# design.net
KiCad netlist of a schematic drawn in Altium Designer
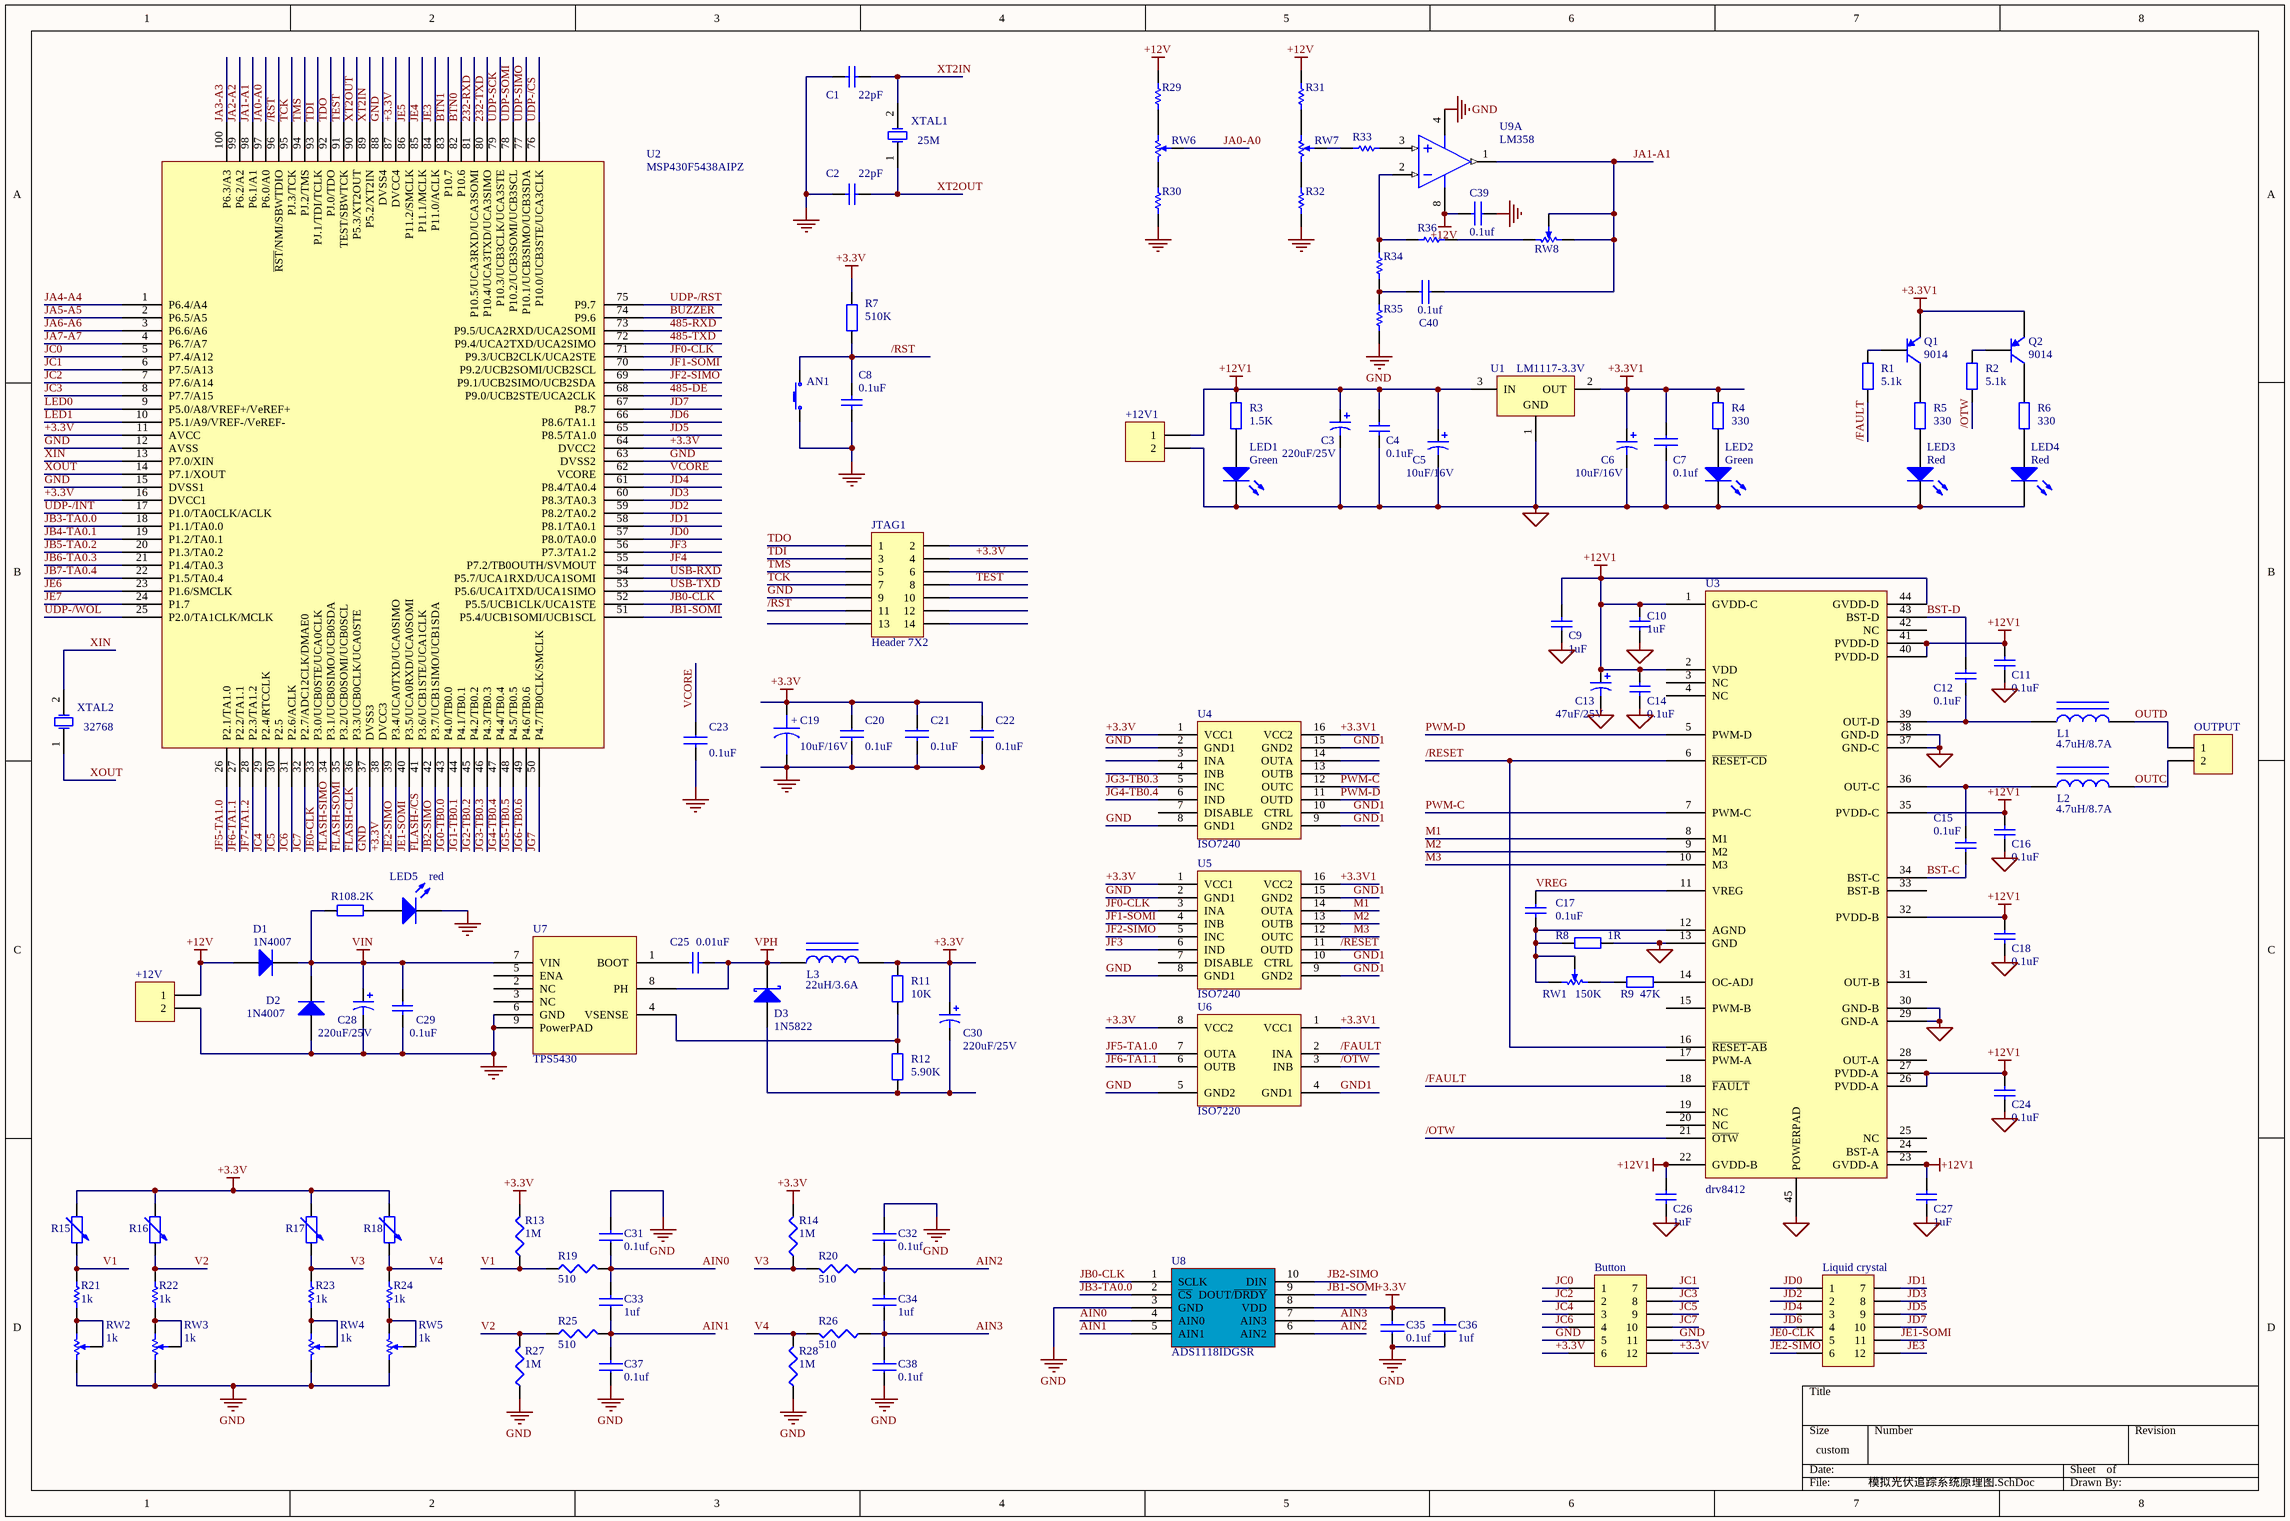
[diagram p0: 模拟光伏追踪系统原理图.SchDoc]

(export (version "E")
  (design (tool "Eeschema 10.0.6"))
  (components
    (comp (ref "+12V")
      (value "Comment")
      (footprint "接线端子")
      (description "Header, 2-Pin")
      (fields (field (name "PUBLISHER") "Altium Limited"))
      (libsource (lib "Miscellaneous Connectors") (part "Header 2"))
    )
    (comp (ref "+12V1")
      (value "Comment")
      (footprint "接线端子")
      (description "Header, 2-Pin")
      (fields (field (name "PUBLISHER") "Altium Limited"))
      (libsource (lib "Miscellaneous Connectors") (part "Header 2"))
    )
    (comp (ref "AN1") (value "key") (footprint "AN6X6") (libsource (lib "*") (part "Key_2")))
    (comp (ref "Button")
      (value "Header 6X2A")
      (footprint "PMOD")
      (description "Header, 6-Pin, Dual row")
      (fields (field (name "PUBLISHER") "Altium Limited"))
      (libsource (lib "Miscellaneous Connectors") (part "Header 6X2A"))
    )
    (comp (ref "C1")
      (value "22pF")
      (footprint "0805C")
      (description "Capacitor")
      (fields (field (name "Comment") "Cap") (field (name "PUBLISHER") "Altium Limited"))
      (libsource (lib "Miscellaneous Devices") (part "Cap"))
    )
    (comp (ref "C2")
      (value "22pF")
      (footprint "0805C")
      (description "Capacitor")
      (fields (field (name "Comment") "Cap") (field (name "PUBLISHER") "Altium Limited"))
      (libsource (lib "Miscellaneous Devices") (part "Cap"))
    )
    (comp (ref "C3")
      (value "220uF/25V")
      (footprint "CD-220uF-25V")
      (description "Polarized Capacitor (Radial)")
      (fields (field (name "Comment") "Cap Pol1") (field (name "PUBLISHER") "Altium Limited"))
      (libsource (lib "Miscellaneous Devices") (part "Cap Pol1"))
    )
    (comp (ref "C4")
      (value "0.1uF")
      (footprint "0805C")
      (description "Capacitor")
      (fields (field (name "Comment") "Cap") (field (name "PUBLISHER") "Altium Limited"))
      (libsource (lib "Miscellaneous Devices") (part "Cap"))
    )
    (comp (ref "C5")
      (value "10uF/16V")
      (footprint "A3216")
      (description "Polarized Capacitor (Radial)")
      (fields (field (name "PUBLISHER") "Altium Limited"))
      (libsource (lib "Miscellaneous Devices") (part "Cap Pol1"))
    )
    (comp (ref "C6")
      (value "10uF/16V")
      (footprint "A3216")
      (description "Polarized Capacitor (Radial)")
      (fields (field (name "PUBLISHER") "Altium Limited"))
      (libsource (lib "Miscellaneous Devices") (part "Cap Pol1"))
    )
    (comp (ref "C7") (value "0.1uf") (footprint "0805C") (libsource (lib "General") (part "Cap")))
    (comp (ref "C8")
      (value "0.1uF")
      (footprint "0805C")
      (description "Capacitor")
      (fields (field (name "Comment") "Cap") (field (name "PUBLISHER") "Altium Limited"))
      (libsource (lib "Miscellaneous Devices") (part "Cap"))
    )
    (comp (ref "C9")
      (value "1uF")
      (footprint "0805C")
      (description "Capacitor")
      (fields (field (name "Comment") "Cap") (field (name "PUBLISHER") "Altium Limited"))
      (libsource (lib "Miscellaneous Devices") (part "Cap"))
    )
    (comp (ref "C10")
      (value "1uF")
      (footprint "0805C")
      (description "Capacitor")
      (fields (field (name "Comment") "Cap") (field (name "PUBLISHER") "Altium Limited"))
      (libsource (lib "Miscellaneous Devices") (part "Cap"))
    )
    (comp (ref "C11")
      (value "0.1uF")
      (footprint "0805C")
      (description "Capacitor")
      (fields (field (name "Comment") "Cap") (field (name "PUBLISHER") "Altium Limited"))
      (libsource (lib "Miscellaneous Devices") (part "Cap"))
    )
    (comp (ref "C12")
      (value "0.1uF")
      (footprint "0805C")
      (description "Capacitor")
      (fields (field (name "Comment") "Cap") (field (name "PUBLISHER") "Altium Limited"))
      (libsource (lib "Miscellaneous Devices") (part "Cap"))
    )
    (comp (ref "C13")
      (value "47uF/25V")
      (footprint "CD-220uF-25V")
      (description "Polarized Capacitor (Radial)")
      (fields (field (name "Comment") "Cap Pol1") (field (name "PUBLISHER") "Altium Limited"))
      (libsource (lib "Miscellaneous Devices") (part "Cap Pol1"))
    )
    (comp (ref "C14")
      (value "0.1uF")
      (footprint "0805C")
      (description "Capacitor")
      (fields (field (name "Comment") "Cap") (field (name "PUBLISHER") "Altium Limited"))
      (libsource (lib "Miscellaneous Devices") (part "Cap"))
    )
    (comp (ref "C15")
      (value "0.1uF")
      (footprint "0805C")
      (description "Capacitor")
      (fields (field (name "Comment") "Cap") (field (name "PUBLISHER") "Altium Limited"))
      (libsource (lib "Miscellaneous Devices") (part "Cap"))
    )
    (comp (ref "C16")
      (value "0.1uF")
      (footprint "0805C")
      (description "Capacitor")
      (fields (field (name "Comment") "Cap") (field (name "PUBLISHER") "Altium Limited"))
      (libsource (lib "Miscellaneous Devices") (part "Cap"))
    )
    (comp (ref "C17")
      (value "0.1uF")
      (footprint "0805C")
      (description "Capacitor")
      (fields (field (name "Comment") "Cap") (field (name "PUBLISHER") "Altium Limited"))
      (libsource (lib "Miscellaneous Devices") (part "Cap"))
    )
    (comp (ref "C18")
      (value "0.1uF")
      (footprint "0805C")
      (description "Capacitor")
      (fields (field (name "Comment") "Cap") (field (name "PUBLISHER") "Altium Limited"))
      (libsource (lib "Miscellaneous Devices") (part "Cap"))
    )
    (comp (ref "C19")
      (value "10uF/16V")
      (footprint "A3216")
      (description "Capacitor")
      (libsource (lib "*") (part "CAPACITOR POL"))
    )
    (comp (ref "C20") (value "0.1uF") (footprint "0805C") (libsource (lib "*") (part "CC_0.1U_16V_X7R_0603")))
    (comp (ref "C21") (value "0.1uF") (footprint "0805C") (libsource (lib "*") (part "CC_0.1U_16V_X7R_0603")))
    (comp (ref "C22") (value "0.1uF") (footprint "0805C") (libsource (lib "*") (part "CC_0.1U_16V_X7R_0603")))
    (comp (ref "C23")
      (value "0.1uF")
      (footprint "0805C")
      (libsource (lib "*") (part "CC_0.01U_16V_X7R_0603"))
    )
    (comp (ref "C24")
      (value "0.1uF")
      (footprint "0805C")
      (description "Capacitor")
      (fields (field (name "Comment") "Cap") (field (name "PUBLISHER") "Altium Limited"))
      (libsource (lib "Miscellaneous Devices") (part "Cap"))
    )
    (comp (ref "C25")
      (value "0.01uF")
      (footprint "0805C")
      (description "Capacitor")
      (fields (field (name "Comment") "Cap") (field (name "PUBLISHER") "Altium Limited"))
      (libsource (lib "Miscellaneous Devices") (part "Cap"))
    )
    (comp (ref "C26")
      (value "1uF")
      (footprint "0805C")
      (description "Capacitor")
      (fields (field (name "Comment") "Cap") (field (name "PUBLISHER") "Altium Limited"))
      (libsource (lib "Miscellaneous Devices") (part "Cap"))
    )
    (comp (ref "C27")
      (value "1uF")
      (footprint "0805C")
      (description "Capacitor")
      (fields (field (name "Comment") "Cap") (field (name "PUBLISHER") "Altium Limited"))
      (libsource (lib "Miscellaneous Devices") (part "Cap"))
    )
    (comp (ref "C28")
      (value "220uF/25V")
      (footprint "CD-220uF-25V")
      (description "Polarized Capacitor (Radial)")
      (fields (field (name "Comment") "Cap Pol1") (field (name "PUBLISHER") "Altium Limited"))
      (libsource (lib "Miscellaneous Devices") (part "Cap Pol1"))
    )
    (comp (ref "C29")
      (value "0.1uF")
      (footprint "0805C")
      (description "Capacitor")
      (fields (field (name "Comment") "Cap") (field (name "PUBLISHER") "Altium Limited"))
      (libsource (lib "Miscellaneous Devices") (part "Cap"))
    )
    (comp (ref "C30")
      (value "220uF/25V")
      (footprint "CD-220uF-25V")
      (description "Polarized Capacitor (Radial)")
      (fields (field (name "Comment") "Cap Pol1") (field (name "PUBLISHER") "Altium Limited"))
      (libsource (lib "Miscellaneous Devices") (part "Cap Pol1"))
    )
    (comp (ref "C31") (value "0.1uf") (footprint "0805C") (libsource (lib "General") (part "Cap")))
    (comp (ref "C32") (value "0.1uf") (footprint "0805C") (libsource (lib "General") (part "Cap")))
    (comp (ref "C33") (value "1uf") (footprint "0805C") (libsource (lib "General") (part "Cap")))
    (comp (ref "C34") (value "1uf") (footprint "0805C") (libsource (lib "General") (part "Cap")))
    (comp (ref "C35") (value "0.1uf") (footprint "0805C") (libsource (lib "General") (part "Cap")))
    (comp (ref "C36") (value "1uf") (footprint "0805C") (libsource (lib "General") (part "Cap")))
    (comp (ref "C37") (value "0.1uf") (footprint "0805C") (libsource (lib "General") (part "Cap")))
    (comp (ref "C38") (value "0.1uf") (footprint "0805C") (libsource (lib "General") (part "Cap")))
    (comp (ref "C39") (value "0.1uf") (footprint "0805C") (libsource (lib "General") (part "Cap")))
    (comp (ref "C40") (value "0.1uf") (footprint "0805C") (libsource (lib "General") (part "Cap")))
    (comp (ref "D1") (value "1N4007") (footprint "D1206") (libsource (lib "Sch") (part "DIODE")))
    (comp (ref "D2") (value "1N4007") (footprint "D1206") (libsource (lib "Sch") (part "DIODE")))
    (comp (ref "D3")
      (value "D Schottky")
      (footprint "D1206")
      (description "Schottky Diode")
      (fields (field (name "ALTIUM_UNNAMED_1") "1N5822") (field (name "PUBLISHER") "Altium Limited"))
      (libsource (lib "Miscellaneous Devices") (part "D Schottky"))
    )
    (comp (ref "JTAG1")
      (value "Header 7X2")
      (footprint "HDR2X7")
      (description "Header, 7-Pin, Dual row")
      (fields (field (name "PUBLISHER") "Altium Limited"))
      (libsource (lib "Miscellaneous Connectors") (part "Header 7X2"))
    )
    (comp (ref "L1")
      (value "4.7uH/8.7A")
      (footprint "CDRH127")
      (description "Magnetic-Core Inductor")
      (fields (field (name "Comment") "Inductor Iron") (field (name "PUBLISHER") "Altium Limited"))
      (libsource (lib "Miscellaneous Devices") (part "Inductor Iron"))
    )
    (comp (ref "L2")
      (value "4.7uH/8.7A")
      (footprint "CDRH127")
      (description "Magnetic-Core Inductor")
      (fields (field (name "Comment") "Inductor Iron") (field (name "PUBLISHER") "Altium Limited"))
      (libsource (lib "Miscellaneous Devices") (part "Inductor Iron"))
    )
    (comp (ref "L3")
      (value "22uH/3.6A")
      (footprint "CDRH127")
      (description "Magnetic-Core Inductor")
      (fields (field (name "Comment") "Inductor Iron") (field (name "PUBLISHER") "Altium Limited"))
      (libsource (lib "Miscellaneous Devices") (part "Inductor Iron"))
    )
    (comp (ref "LED1")
      (value "~")
      (footprint "0805LED")
      (description "Typical RED, GREEN, YELLOW, AMBER GaAs LED")
      (fields (field (name "ALTIUM_UNNAMED_1") "Green") (field (name "PUBLISHER") "Altium Limited"))
      (libsource (lib "Miscellaneous Devices") (part "LED2"))
    )
    (comp (ref "LED2")
      (value "~")
      (footprint "0805LED")
      (description "Typical RED, GREEN, YELLOW, AMBER GaAs LED")
      (fields (field (name "ALTIUM_UNNAMED_1") "Green") (field (name "PUBLISHER") "Altium Limited"))
      (libsource (lib "Miscellaneous Devices") (part "LED2"))
    )
    (comp (ref "LED3")
      (value "~")
      (footprint "0805LED")
      (description "Typical RED, GREEN, YELLOW, AMBER GaAs LED")
      (fields (field (name "ALTIUM_UNNAMED_1") "Red") (field (name "PUBLISHER") "Altium Limited"))
      (libsource (lib "Miscellaneous Devices") (part "LED2"))
    )
    (comp (ref "LED4")
      (value "~")
      (footprint "0805LED")
      (description "Typical RED, GREEN, YELLOW, AMBER GaAs LED")
      (fields (field (name "ALTIUM_UNNAMED_1") "Red") (field (name "PUBLISHER") "Altium Limited"))
      (libsource (lib "Miscellaneous Devices") (part "LED2"))
    )
    (comp (ref "LED5")
      (value "~")
      (footprint "0805LED")
      (description "Typical RED, GREEN, YELLOW, AMBER GaAs LED")
      (fields (field (name "ALTIUM_UNNAMED_1") "red") (field (name "PUBLISHER") "Altium Limited"))
      (libsource (lib "Miscellaneous Devices") (part "LED2"))
    )
    (comp (ref "Liquid crystal")
      (value "Header 6X2A")
      (footprint "PMOD")
      (description "Header, 6-Pin, Dual row")
      (fields (field (name "PUBLISHER") "Altium Limited"))
      (libsource (lib "Miscellaneous Connectors") (part "Header 6X2A"))
    )
    (comp (ref "OUTPUT")
      (value "Comment")
      (footprint "接线端子")
      (description "Header, 2-Pin")
      (fields (field (name "PUBLISHER") "Altium Limited"))
      (libsource (lib "") (part "Header 2_1"))
    )
    (comp (ref "Q1")
      (value "9014")
      (footprint "SOT-23B")
      (description "PNP Bipolar Transistor")
      (fields (field (name "PUBLISHER") "Altium Limited"))
      (libsource (lib "Miscellaneous Devices") (part "PNP"))
    )
    (comp (ref "Q2")
      (value "9014")
      (footprint "SOT-23B")
      (description "PNP Bipolar Transistor")
      (fields (field (name "PUBLISHER") "Altium Limited"))
      (libsource (lib "Miscellaneous Devices") (part "PNP"))
    )
    (comp (ref "R1")
      (value "5.1k")
      (footprint "0805R")
      (description "Resistor")
      (fields (field (name "Comment") "Res2") (field (name "PUBLISHER") "Altium Limited"))
      (libsource (lib "") (part "Res2_2"))
    )
    (comp (ref "R2")
      (value "5.1k")
      (footprint "0805R")
      (description "Resistor")
      (fields (field (name "Comment") "Res2") (field (name "PUBLISHER") "Altium Limited"))
      (libsource (lib "") (part "Res2_2"))
    )
    (comp (ref "R3")
      (value "1.5K")
      (footprint "0805R")
      (description "Resistor")
      (fields (field (name "Comment") "Res2") (field (name "PUBLISHER") "Altium Limited"))
      (libsource (lib "Miscellaneous Devices") (part "Res2"))
    )
    (comp (ref "R4")
      (value "330")
      (footprint "0805R")
      (description "Resistor")
      (fields (field (name "Comment") "Res2") (field (name "PUBLISHER") "Altium Limited"))
      (libsource (lib "") (part "Res2_2"))
    )
    (comp (ref "R5")
      (value "330")
      (footprint "0805R")
      (description "Resistor")
      (fields (field (name "Comment") "Res2") (field (name "PUBLISHER") "Altium Limited"))
      (libsource (lib "") (part "Res2_2"))
    )
    (comp (ref "R6")
      (value "330")
      (footprint "0805R")
      (description "Resistor")
      (fields (field (name "Comment") "Res2") (field (name "PUBLISHER") "Altium Limited"))
      (libsource (lib "") (part "Res2_2"))
    )
    (comp (ref "R7")
      (value "510K")
      (footprint "0805R")
      (description "Resistor")
      (fields (field (name "Comment") "Res2") (field (name "PUBLISHER") "Altium Limited"))
      (libsource (lib "Miscellaneous Devices") (part "Res2"))
    )
    (comp (ref "R8")
      (value "1R")
      (footprint "0805R")
      (description "Resistor")
      (fields (field (name "Comment") "Res2") (field (name "PUBLISHER") "Altium Limited"))
      (libsource (lib "") (part "Res2_1"))
    )
    (comp (ref "R9")
      (value "47K")
      (footprint "0805R")
      (description "Resistor")
      (fields (field (name "Comment") "Res2") (field (name "PUBLISHER") "Altium Limited"))
      (libsource (lib "") (part "Res2_1"))
    )
    (comp (ref "R10")
      (value "8.2K")
      (footprint "0805R")
      (description "Resistor")
      (fields (field (name "Comment") "Res2") (field (name "PUBLISHER") "Altium Limited"))
      (libsource (lib "") (part "Res2_1"))
    )
    (comp (ref "R11")
      (value "10K")
      (footprint "0805R")
      (description "Resistor")
      (fields (field (name "Comment") "Res2") (field (name "PUBLISHER") "Altium Limited"))
      (libsource (lib "Miscellaneous Devices") (part "Res2"))
    )
    (comp (ref "R12")
      (value "5.90K")
      (footprint "0805R")
      (description "Resistor")
      (fields (field (name "Comment") "Res2") (field (name "PUBLISHER") "Altium Limited"))
      (libsource (lib "Miscellaneous Devices") (part "Res2"))
    )
    (comp (ref "R13") (value "1M") (footprint "0805R") (libsource (lib "General") (part "Res1")))
    (comp (ref "R14") (value "1M") (footprint "0805R") (libsource (lib "General") (part "Res1")))
    (comp (ref "R15")
      (value "~")
      (footprint "RL")
      (description "Variable Resistor")
      (fields (field (name "PUBLISHER") "Altium Limited"))
      (libsource (lib "Miscellaneous Devices") (part "Res Adj2"))
    )
    (comp (ref "R16")
      (value "~")
      (footprint "RL")
      (description "Variable Resistor")
      (fields (field (name "PUBLISHER") "Altium Limited"))
      (libsource (lib "Miscellaneous Devices") (part "Res Adj2"))
    )
    (comp (ref "R17")
      (value "~")
      (footprint "RL")
      (description "Variable Resistor")
      (fields (field (name "PUBLISHER") "Altium Limited"))
      (libsource (lib "Miscellaneous Devices") (part "Res Adj2"))
    )
    (comp (ref "R18")
      (value "~")
      (footprint "RL")
      (description "Variable Resistor")
      (fields (field (name "PUBLISHER") "Altium Limited"))
      (libsource (lib "Miscellaneous Devices") (part "Res Adj2"))
    )
    (comp (ref "R19") (value "510") (footprint "0805R") (libsource (lib "General") (part "Res1")))
    (comp (ref "R20") (value "510") (footprint "0805R") (libsource (lib "General") (part "Res1")))
    (comp (ref "R21") (value "1k") (footprint "0805R") (libsource (lib "General") (part "Res2")))
    (comp (ref "R22") (value "1k") (footprint "0805R") (libsource (lib "General") (part "Res2")))
    (comp (ref "R23") (value "1k") (footprint "0805R") (libsource (lib "General") (part "Res2")))
    (comp (ref "R24") (value "1k") (footprint "0805R") (libsource (lib "General") (part "Res2")))
    (comp (ref "R25") (value "510") (footprint "0805R") (libsource (lib "General") (part "Res1")))
    (comp (ref "R26") (value "510") (footprint "0805R") (libsource (lib "General") (part "Res1")))
    (comp (ref "R27") (value "1M") (footprint "0805R") (libsource (lib "General") (part "Res1")))
    (comp (ref "R28") (value "1M") (footprint "0805R") (libsource (lib "General") (part "Res1")))
    (comp (ref "R29") (value "~") (footprint "0805R") (libsource (lib "General") (part "Res2")))
    (comp (ref "R30") (value "~") (footprint "0805R") (libsource (lib "General") (part "Res2")))
    (comp (ref "R31") (value "~") (footprint "0805R") (libsource (lib "General") (part "Res2")))
    (comp (ref "R32") (value "~") (footprint "0805R") (libsource (lib "General") (part "Res2")))
    (comp (ref "R33") (value "~") (footprint "0805R") (libsource (lib "General") (part "Res2")))
    (comp (ref "R34") (value "~") (footprint "0805R") (libsource (lib "General") (part "Res2")))
    (comp (ref "R35") (value "~") (footprint "0805R") (libsource (lib "General") (part "Res2")))
    (comp (ref "R36") (value "~") (footprint "0805R") (libsource (lib "General") (part "Res2")))
    (comp (ref "RW1") (value "150K") (footprint "3362RW") (libsource (lib "General") (part "Res adj1")))
    (comp (ref "RW2") (value "1k") (footprint "3296W") (libsource (lib "General") (part "Res adj1")))
    (comp (ref "RW3") (value "1k") (footprint "3296W") (libsource (lib "General") (part "Res adj1")))
    (comp (ref "RW4") (value "1k") (footprint "3296W") (libsource (lib "General") (part "Res adj1")))
    (comp (ref "RW5") (value "1k") (footprint "3296W") (libsource (lib "General") (part "Res adj1")))
    (comp (ref "RW6") (value "~") (footprint "3296W") (libsource (lib "General") (part "Res adj1")))
    (comp (ref "RW7") (value "~") (footprint "3296W") (libsource (lib "General") (part "Res adj1")))
    (comp (ref "RW8") (value "~") (footprint "3296W") (libsource (lib "General") (part "Res adj1")))
    (comp (ref "U1")
      (value "LM1117-3.3V")
      (footprint "SOT-223")
      (description "800mA Low-Dropout Linear Regulator")
      (fields
        (field (name "PARTNUMBER") "LM1117T-3.3")
        (field (name "MANUFACTURER") "National Semiconductor")
        (field (name "PUBLISHER") "Altium Limited")
      )
      (libsource (lib "NSC LDO") (part "LM1117T-3.3"))
    )
    (comp (ref "U2")
      (value "MSP430F5438AIPZ")
      (footprint "TSQFP50P1600X1600X160-100N")
      (libsource (lib "my") (part "MSP430F5438AIPZ"))
    )
    (comp (ref "U3") (value "drv8412") (footprint "SOP127P600-8N") (libsource (lib "my") (part "drv8412")))
    (comp (ref "U4") (value "ISO7240") (footprint "SOIC-16") (libsource (lib "my") (part "ISO7240")))
    (comp (ref "U5") (value "ISO7240") (footprint "SOIC-16") (libsource (lib "my") (part "ISO7240")))
    (comp (ref "U6") (value "ISO7220") (footprint "SOIC-8") (libsource (lib "my") (part "ISO7220")))
    (comp (ref "U7")
      (value "TPS5430")
      (footprint "SOIC127P600X170_HS-8N")
      (libsource (lib "my") (part "TPS5430"))
    )
    (comp (ref "U8")
      (value "ADS1118IDGSR")
      (footprint "VSSOP-10")
      (libsource (lib "2013-MSP430库") (part "ADS118"))
    )
    (comp (ref "U9") (value "LM358") (footprint "SOIC-8") (libsource (lib "microchip") (part "LF353M")))
    (comp (ref "XTAL1")
      (value "XTAL")
      (footprint "XTAL-A")
      (description "Crystal Oscillator")
      (fields (field (name "ALTIUM_UNNAMED_1") "25M") (field (name "PUBLISHER") "Altium Limited"))
      (libsource (lib "Miscellaneous Devices") (part "XTAL"))
    )
    (comp (ref "XTAL2")
      (value "XTAL")
      (footprint "XTAL-B")
      (description "Crystal Oscillator")
      (fields (field (name "ALTIUM_UNNAMED_1") "32768") (field (name "PUBLISHER") "Altium Limited"))
      (libsource (lib "Miscellaneous Devices") (part "XTAL"))
    )
  )
  (nets
    (net (code "1") (name "+3.3V") (class "Default")
      (node (ref "Button") (pin "12") (pinfunction "12_12") (pintype "passive"))
      (node (ref "Button") (pin "6") (pinfunction "6_6") (pintype "passive"))
      (node (ref "C19") (pin "1") (pinfunction "1_1") (pintype "passive"))
      (node (ref "C20") (pin "1") (pinfunction "1_1") (pintype "passive"))
      (node (ref "C21") (pin "1") (pinfunction "1_1") (pintype "passive"))
      (node (ref "C22") (pin "1") (pinfunction "1_1") (pintype "passive"))
      (node (ref "C30") (pin "1") (pinfunction "1_1") (pintype "passive"))
      (node (ref "C35") (pin "2") (pinfunction "2_2") (pintype "passive"))
      (node (ref "C36") (pin "2") (pinfunction "2_2") (pintype "passive"))
      (node (ref "JTAG1") (pin "4") (pinfunction "4_4") (pintype "passive"))
      (node (ref "L3") (pin "2") (pinfunction "2_2") (pintype "passive"))
      (node (ref "R11") (pin "2") (pinfunction "2_2") (pintype "passive"))
      (node (ref "R13") (pin "2") (pinfunction "2_2") (pintype "passive"))
      (node (ref "R14") (pin "2") (pinfunction "2_2") (pintype "passive"))
      (node (ref "R15") (pin "1") (pinfunction "1_1") (pintype "passive"))
      (node (ref "R16") (pin "1") (pinfunction "1_1") (pintype "passive"))
      (node (ref "R17") (pin "1") (pinfunction "1_1") (pintype "passive"))
      (node (ref "R18") (pin "1") (pinfunction "1_1") (pintype "passive"))
      (node (ref "R7") (pin "2") (pinfunction "2_2") (pintype "passive"))
      (node (ref "U2") (pin "11") (pinfunction "AVCC_11") (pintype "passive"))
      (node (ref "U2") (pin "16") (pinfunction "DVCC1_16") (pintype "passive"))
      (node (ref "U2") (pin "38") (pinfunction "DVCC3_38") (pintype "passive"))
      (node (ref "U2") (pin "64") (pinfunction "DVCC2_64") (pintype "passive"))
      (node (ref "U2") (pin "87") (pinfunction "DVCC4_87") (pintype "passive"))
      (node (ref "U4") (pin "1") (pinfunction "VCC1_1") (pintype "passive"))
      (node (ref "U5") (pin "1") (pinfunction "VCC1_1") (pintype "passive"))
      (node (ref "U6") (pin "8") (pinfunction "VCC2_8") (pintype "passive"))
      (node (ref "U8") (pin "8") (pinfunction "VDD_8") (pintype "passive"))
    )
    (net (code "2") (name "+3.3V1") (class "Default")
      (node (ref "C6") (pin "1") (pinfunction "1_1") (pintype "passive"))
      (node (ref "C7") (pin "2") (pinfunction "2_2") (pintype "passive"))
      (node (ref "Q1") (pin "3") (pinfunction "E_3") (pintype "passive"))
      (node (ref "Q2") (pin "3") (pinfunction "E_3") (pintype "passive"))
      (node (ref "R4") (pin "1") (pinfunction "1_1") (pintype "passive"))
      (node (ref "U1") (pin "2") (pinfunction "OUT_2") (pintype "power_in"))
      (node (ref "U4") (pin "16") (pinfunction "VCC2_16") (pintype "passive"))
      (node (ref "U5") (pin "16") (pinfunction "VCC2_16") (pintype "passive"))
      (node (ref "U6") (pin "1") (pinfunction "VCC1_1") (pintype "passive"))
    )
    (net (code "3") (name "+12V") (class "Default")
      (node (ref "+12V") (pin "1") (pinfunction "1_1") (pintype "passive"))
      (node (ref "C39") (pin "2") (pinfunction "2_2") (pintype "passive"))
      (node (ref "D1") (pin "1") (pinfunction "A_1") (pintype "passive"))
      (node (ref "R29") (pin "2") (pinfunction "2_2") (pintype "passive"))
      (node (ref "R31") (pin "2") (pinfunction "2_2") (pintype "passive"))
      (node (ref "U9") (pin "8") (pinfunction "V+_8") (pintype "power_in"))
    )
    (net (code "4") (name "+12V1") (class "Default")
      (node (ref "+12V1") (pin "1") (pinfunction "1_1") (pintype "passive"))
      (node (ref "C10") (pin "2") (pinfunction "2_2") (pintype "passive"))
      (node (ref "C11") (pin "2") (pinfunction "2_2") (pintype "passive"))
      (node (ref "C13") (pin "1") (pinfunction "1_1") (pintype "passive"))
      (node (ref "C14") (pin "2") (pinfunction "2_2") (pintype "passive"))
      (node (ref "C16") (pin "2") (pinfunction "2_2") (pintype "passive"))
      (node (ref "C18") (pin "2") (pinfunction "2_2") (pintype "passive"))
      (node (ref "C24") (pin "2") (pinfunction "2_2") (pintype "passive"))
      (node (ref "C26") (pin "2") (pinfunction "2_2") (pintype "passive"))
      (node (ref "C27") (pin "2") (pinfunction "2_2") (pintype "passive"))
      (node (ref "C3") (pin "1") (pinfunction "1_1") (pintype "passive"))
      (node (ref "C4") (pin "2") (pinfunction "2_2") (pintype "passive"))
      (node (ref "C5") (pin "1") (pinfunction "1_1") (pintype "passive"))
      (node (ref "C9") (pin "2") (pinfunction "2_2") (pintype "passive"))
      (node (ref "R3") (pin "2") (pinfunction "2_2") (pintype "passive"))
      (node (ref "U1") (pin "3") (pinfunction "IN_3") (pintype "power_in"))
      (node (ref "U3") (pin "1") (pinfunction "GVDD-C_1") (pintype "passive"))
      (node (ref "U3") (pin "2") (pinfunction "VDD_2") (pintype "passive"))
      (node (ref "U3") (pin "22") (pinfunction "GVDD-B_22") (pintype "passive"))
      (node (ref "U3") (pin "23") (pinfunction "GVDD-A_23") (pintype "passive"))
      (node (ref "U3") (pin "26") (pinfunction "PVDD-A_26") (pintype "passive"))
      (node (ref "U3") (pin "27") (pinfunction "PVDD-A_27") (pintype "passive"))
      (node (ref "U3") (pin "32") (pinfunction "PVDD-B_32") (pintype "passive"))
      (node (ref "U3") (pin "35") (pinfunction "PVDD-C_35") (pintype "passive"))
      (node (ref "U3") (pin "40") (pinfunction "PVDD-D_40") (pintype "passive"))
      (node (ref "U3") (pin "41") (pinfunction "PVDD-D_41") (pintype "passive"))
      (node (ref "U3") (pin "44") (pinfunction "GVDD-D_44") (pintype "passive"))
    )
    (net (code "5") (name "/232-RXD") (class "Default")
      (node (ref "U2") (pin "81") (pinfunction "P10.5/UCA3RXD/UCA3SOMI_81") (pintype "passive"))
    )
    (net (code "6") (name "/232-TXD") (class "Default")
      (node (ref "U2") (pin "80") (pinfunction "P10.4/UCA3TXD/UCA3SIMO_80") (pintype "passive"))
    )
    (net (code "7") (name "/485-DE") (class "Default")
      (node (ref "U2") (pin "68") (pinfunction "P9.0/UCB2STE/UCA2CLK_68") (pintype "passive"))
    )
    (net (code "8") (name "/485-RXD") (class "Default")
      (node (ref "U2") (pin "73") (pinfunction "P9.5/UCA2RXD/UCA2SOMI_73") (pintype "passive"))
    )
    (net (code "9") (name "/485-TXD") (class "Default")
      (node (ref "U2") (pin "72") (pinfunction "P9.4/UCA2TXD/UCA2SIMO_72") (pintype "passive"))
    )
    (net (code "10") (name "/AIN0") (class "Default")
      (node (ref "C31") (pin "1") (pinfunction "1_1") (pintype "passive"))
      (node (ref "C33") (pin "2") (pinfunction "2_2") (pintype "passive"))
      (node (ref "R19") (pin "2") (pinfunction "2_2") (pintype "passive"))
      (node (ref "U8") (pin "4") (pinfunction "AIN0_4") (pintype "passive"))
    )
    (net (code "11") (name "/AIN1") (class "Default")
      (node (ref "C33") (pin "1") (pinfunction "1_1") (pintype "passive"))
      (node (ref "C37") (pin "2") (pinfunction "2_2") (pintype "passive"))
      (node (ref "R25") (pin "2") (pinfunction "2_2") (pintype "passive"))
      (node (ref "U8") (pin "5") (pinfunction "AIN1_5") (pintype "passive"))
    )
    (net (code "12") (name "/AIN2") (class "Default")
      (node (ref "C32") (pin "1") (pinfunction "1_1") (pintype "passive"))
      (node (ref "C34") (pin "2") (pinfunction "2_2") (pintype "passive"))
      (node (ref "R20") (pin "1") (pinfunction "1_1") (pintype "passive"))
      (node (ref "U8") (pin "6") (pinfunction "AIN2_6") (pintype "passive"))
    )
    (net (code "13") (name "/AIN3") (class "Default")
      (node (ref "C34") (pin "1") (pinfunction "1_1") (pintype "passive"))
      (node (ref "C38") (pin "2") (pinfunction "2_2") (pintype "passive"))
      (node (ref "R26") (pin "1") (pinfunction "1_1") (pintype "passive"))
      (node (ref "U8") (pin "7") (pinfunction "AIN3_7") (pintype "passive"))
    )
    (net (code "14") (name "/BST-C") (class "Default")
      (node (ref "C15") (pin "1") (pinfunction "1_1") (pintype "passive"))
      (node (ref "U3") (pin "34") (pinfunction "BST-C_34") (pintype "passive"))
    )
    (net (code "15") (name "/BST-D") (class "Default")
      (node (ref "C12") (pin "2") (pinfunction "2_2") (pintype "passive"))
      (node (ref "U3") (pin "43") (pinfunction "BST-D_43") (pintype "passive"))
    )
    (net (code "16") (name "/BTN0") (class "Default")
      (node (ref "U2") (pin "82") (pinfunction "P10.6_82") (pintype "passive"))
    )
    (net (code "17") (name "/BTN1") (class "Default")
      (node (ref "U2") (pin "83") (pinfunction "P10.7_83") (pintype "passive"))
    )
    (net (code "18") (name "/BUZZER") (class "Default")
      (node (ref "U2") (pin "74") (pinfunction "P9.6_74") (pintype "passive"))
    )
    (net (code "19") (name "/FLASH-CLK") (class "Default")
      (node (ref "U2") (pin "36") (pinfunction "P3.3/UCB0CLK/UCA0STE_36") (pintype "passive"))
    )
    (net (code "20") (name "/FLASH-SIMO") (class "Default")
      (node (ref "U2") (pin "34") (pinfunction "P3.1/UCB0SIMO/UCB0SDA_34") (pintype "passive"))
    )
    (net (code "21") (name "/FLASH-SOMI") (class "Default")
      (node (ref "U2") (pin "35") (pinfunction "P3.2/UCB0SOMI/UCB0SCL_35") (pintype "passive"))
    )
    (net (code "22") (name "/FLASH-{slash}CS") (class "Default")
      (node (ref "U2") (pin "41") (pinfunction "P3.6/UCB1STE/UCA1CLK_41") (pintype "passive"))
    )
    (net (code "23") (name "/JA0-A0") (class "Default")
      (node (ref "RW6") (pin "2") (pinfunction "2_2") (pintype "passive"))
      (node (ref "U2") (pin "97") (pinfunction "P6.0/A0_97") (pintype "passive"))
    )
    (net (code "24") (name "/JA1-A1") (class "Default")
      (node (ref "C40") (pin "1") (pinfunction "1_1") (pintype "passive"))
      (node (ref "RW8") (pin "1") (pinfunction "1_1") (pintype "passive"))
      (node (ref "RW8") (pin "2") (pinfunction "2_2") (pintype "passive"))
      (node (ref "U2") (pin "98") (pinfunction "P6.1/A1_98") (pintype "passive"))
      (node (ref "U9") (pin "1") (pinfunction "OUTA_1") (pintype "output"))
    )
    (net (code "25") (name "/JA2-A2") (class "Default")
      (node (ref "U2") (pin "99") (pinfunction "P6.2/A2_99") (pintype "passive"))
    )
    (net (code "26") (name "/JA3-A3") (class "Default")
      (node (ref "U2") (pin "100") (pinfunction "P6.3/A3_100") (pintype "passive"))
    )
    (net (code "27") (name "/JA4-A4") (class "Default")
      (node (ref "U2") (pin "1") (pinfunction "P6.4/A4_1") (pintype "passive"))
    )
    (net (code "28") (name "/JA5-A5") (class "Default")
      (node (ref "U2") (pin "2") (pinfunction "P6.5/A5_2") (pintype "passive"))
    )
    (net (code "29") (name "/JA6-A6") (class "Default")
      (node (ref "U2") (pin "3") (pinfunction "P6.6/A6_3") (pintype "passive"))
    )
    (net (code "30") (name "/JA7-A7") (class "Default")
      (node (ref "U2") (pin "4") (pinfunction "P6.7/A7_4") (pintype "passive"))
    )
    (net (code "31") (name "/JB0-CLK") (class "Default")
      (node (ref "U2") (pin "52") (pinfunction "P5.5/UCB1CLK/UCA1STE_52") (pintype "passive"))
      (node (ref "U8") (pin "1") (pinfunction "SCLK_1") (pintype "passive"))
    )
    (net (code "32") (name "/JB1-SOMI") (class "Default")
      (node (ref "U2") (pin "51") (pinfunction "P5.4/UCB1SOMI/UCB1SCL_51") (pintype "passive"))
      (node (ref "U8") (pin "9") (pinfunction "DOUT/~{DRDY}_9") (pintype "passive"))
    )
    (net (code "33") (name "/JB2-SIMO") (class "Default")
      (node (ref "U2") (pin "42") (pinfunction "P3.7/UCB1SIMO/UCB1SDA_42") (pintype "passive"))
      (node (ref "U8") (pin "10") (pinfunction "DIN_10") (pintype "passive"))
    )
    (net (code "34") (name "/JB3-TA0.0") (class "Default")
      (node (ref "U2") (pin "18") (pinfunction "P1.1/TA0.0_18") (pintype "passive"))
      (node (ref "U8") (pin "2") (pinfunction "~{CS}_2") (pintype "passive"))
    )
    (net (code "35") (name "/JB4-TA0.1") (class "Default")
      (node (ref "U2") (pin "19") (pinfunction "P1.2/TA0.1_19") (pintype "passive"))
    )
    (net (code "36") (name "/JB5-TA0.2") (class "Default")
      (node (ref "U2") (pin "20") (pinfunction "P1.3/TA0.2_20") (pintype "passive"))
    )
    (net (code "37") (name "/JB6-TA0.3") (class "Default")
      (node (ref "U2") (pin "21") (pinfunction "P1.4/TA0.3_21") (pintype "passive"))
    )
    (net (code "38") (name "/JB7-TA0.4") (class "Default")
      (node (ref "U2") (pin "22") (pinfunction "P1.5/TA0.4_22") (pintype "passive"))
    )
    (net (code "39") (name "/JC0") (class "Default")
      (node (ref "Button") (pin "1") (pinfunction "1_1") (pintype "passive"))
      (node (ref "U2") (pin "5") (pinfunction "P7.4/A12_5") (pintype "passive"))
    )
    (net (code "40") (name "/JC1") (class "Default")
      (node (ref "Button") (pin "7") (pinfunction "7_7") (pintype "passive"))
      (node (ref "U2") (pin "6") (pinfunction "P7.5/A13_6") (pintype "passive"))
    )
    (net (code "41") (name "/JC2") (class "Default")
      (node (ref "Button") (pin "2") (pinfunction "2_2") (pintype "passive"))
      (node (ref "U2") (pin "7") (pinfunction "P7.6/A14_7") (pintype "passive"))
    )
    (net (code "42") (name "/JC3") (class "Default")
      (node (ref "Button") (pin "8") (pinfunction "8_8") (pintype "passive"))
      (node (ref "U2") (pin "8") (pinfunction "P7.7/A15_8") (pintype "passive"))
    )
    (net (code "43") (name "/JC4") (class "Default")
      (node (ref "Button") (pin "3") (pinfunction "3_3") (pintype "passive"))
      (node (ref "U2") (pin "29") (pinfunction "P2.4/RTCCLK_29") (pintype "passive"))
    )
    (net (code "44") (name "/JC5") (class "Default")
      (node (ref "Button") (pin "9") (pinfunction "9_9") (pintype "passive"))
      (node (ref "U2") (pin "30") (pinfunction "P2.5_30") (pintype "passive"))
    )
    (net (code "45") (name "/JC6") (class "Default")
      (node (ref "Button") (pin "4") (pinfunction "4_4") (pintype "passive"))
      (node (ref "U2") (pin "31") (pinfunction "P2.6/ACLK_31") (pintype "passive"))
    )
    (net (code "46") (name "/JC7") (class "Default")
      (node (ref "Button") (pin "10") (pinfunction "10_10") (pintype "passive"))
      (node (ref "U2") (pin "32") (pinfunction "P2.7/ADC12CLK/DMAE0_32") (pintype "passive"))
    )
    (net (code "47") (name "/JD0") (class "Default")
      (node (ref "Liquid crystal") (pin "1") (pinfunction "1_1") (pintype "passive"))
      (node (ref "U2") (pin "57") (pinfunction "P8.0/TA0.0_57") (pintype "passive"))
    )
    (net (code "48") (name "/JD1") (class "Default")
      (node (ref "Liquid crystal") (pin "7") (pinfunction "7_7") (pintype "passive"))
      (node (ref "U2") (pin "58") (pinfunction "P8.1/TA0.1_58") (pintype "passive"))
    )
    (net (code "49") (name "/JD2") (class "Default")
      (node (ref "Liquid crystal") (pin "2") (pinfunction "2_2") (pintype "passive"))
      (node (ref "U2") (pin "59") (pinfunction "P8.2/TA0.2_59") (pintype "passive"))
    )
    (net (code "50") (name "/JD3") (class "Default")
      (node (ref "Liquid crystal") (pin "8") (pinfunction "8_8") (pintype "passive"))
      (node (ref "U2") (pin "60") (pinfunction "P8.3/TA0.3_60") (pintype "passive"))
    )
    (net (code "51") (name "/JD4") (class "Default")
      (node (ref "Liquid crystal") (pin "3") (pinfunction "3_3") (pintype "passive"))
      (node (ref "U2") (pin "61") (pinfunction "P8.4/TA0.4_61") (pintype "passive"))
    )
    (net (code "52") (name "/JD5") (class "Default")
      (node (ref "Liquid crystal") (pin "9") (pinfunction "9_9") (pintype "passive"))
      (node (ref "U2") (pin "65") (pinfunction "P8.5/TA1.0_65") (pintype "passive"))
    )
    (net (code "53") (name "/JD6") (class "Default")
      (node (ref "Liquid crystal") (pin "4") (pinfunction "4_4") (pintype "passive"))
      (node (ref "U2") (pin "66") (pinfunction "P8.6/TA1.1_66") (pintype "passive"))
    )
    (net (code "54") (name "/JD7") (class "Default")
      (node (ref "Liquid crystal") (pin "10") (pinfunction "10_10") (pintype "passive"))
      (node (ref "U2") (pin "67") (pinfunction "P8.7_67") (pintype "passive"))
    )
    (net (code "55") (name "/JE0-CLK") (class "Default")
      (node (ref "Liquid crystal") (pin "5") (pinfunction "5_5") (pintype "passive"))
      (node (ref "U2") (pin "33") (pinfunction "P3.0/UCB0STE/UCA0CLK_33") (pintype "passive"))
    )
    (net (code "56") (name "/JE1-SOMI") (class "Default")
      (node (ref "Liquid crystal") (pin "11") (pinfunction "11_11") (pintype "passive"))
      (node (ref "U2") (pin "40") (pinfunction "P3.5/UCA0RXD/UCA0SOMI_40") (pintype "passive"))
    )
    (net (code "57") (name "/JE2-SIMO") (class "Default")
      (node (ref "Liquid crystal") (pin "6") (pinfunction "6_6") (pintype "passive"))
      (node (ref "U2") (pin "39") (pinfunction "P3.4/UCA0TXD/UCA0SIMO_39") (pintype "passive"))
    )
    (net (code "58") (name "/JE3") (class "Default")
      (node (ref "Liquid crystal") (pin "12") (pinfunction "12_12") (pintype "passive"))
      (node (ref "U2") (pin "84") (pinfunction "P11.0/ACLK_84") (pintype "passive"))
    )
    (net (code "59") (name "/JE4") (class "Default")
      (node (ref "U2") (pin "85") (pinfunction "P11.1/MCLK_85") (pintype "passive"))
    )
    (net (code "60") (name "/JE5") (class "Default")
      (node (ref "U2") (pin "86") (pinfunction "P11.2/SMCLK_86") (pintype "passive"))
    )
    (net (code "61") (name "/JE6") (class "Default")
      (node (ref "U2") (pin "23") (pinfunction "P1.6/SMCLK_23") (pintype "passive"))
    )
    (net (code "62") (name "/JE7") (class "Default")
      (node (ref "U2") (pin "24") (pinfunction "P1.7_24") (pintype "passive"))
    )
    (net (code "63") (name "/JF0-CLK") (class "Default")
      (node (ref "U2") (pin "71") (pinfunction "P9.3/UCB2CLK/UCA2STE_71") (pintype "passive"))
      (node (ref "U5") (pin "3") (pinfunction "INA_3") (pintype "passive"))
    )
    (net (code "64") (name "/JF1-SOMI") (class "Default")
      (node (ref "U2") (pin "70") (pinfunction "P9.2/UCB2SOMI/UCB2SCL_70") (pintype "passive"))
      (node (ref "U5") (pin "4") (pinfunction "INB_4") (pintype "passive"))
    )
    (net (code "65") (name "/JF2-SIMO") (class "Default")
      (node (ref "U2") (pin "69") (pinfunction "P9.1/UCB2SIMO/UCB2SDA_69") (pintype "passive"))
      (node (ref "U5") (pin "5") (pinfunction "INC_5") (pintype "passive"))
    )
    (net (code "66") (name "/JF3") (class "Default")
      (node (ref "U2") (pin "56") (pinfunction "P7.3/TA1.2_56") (pintype "passive"))
      (node (ref "U5") (pin "6") (pinfunction "IND_6") (pintype "passive"))
    )
    (net (code "67") (name "/JF4") (class "Default")
      (node (ref "U2") (pin "55") (pinfunction "P7.2/TB0OUTH/SVMOUT_55") (pintype "passive"))
    )
    (net (code "68") (name "/JF5-TA1.0") (class "Default")
      (node (ref "U2") (pin "26") (pinfunction "P2.1/TA1.0_26") (pintype "passive"))
      (node (ref "U6") (pin "7") (pinfunction "OUTA_7") (pintype "passive"))
    )
    (net (code "69") (name "/JF6-TA1.1") (class "Default")
      (node (ref "U2") (pin "27") (pinfunction "P2.2/TA1.1_27") (pintype "passive"))
      (node (ref "U6") (pin "6") (pinfunction "OUTB_6") (pintype "passive"))
    )
    (net (code "70") (name "/JF7-TA1.2") (class "Default")
      (node (ref "U2") (pin "28") (pinfunction "P2.3/TA1.2_28") (pintype "passive"))
    )
    (net (code "71") (name "/JG0-TB0.0") (class "Default")
      (node (ref "U2") (pin "43") (pinfunction "P4.0/TB0.0_43") (pintype "passive"))
    )
    (net (code "72") (name "/JG1-TB0.1") (class "Default")
      (node (ref "U2") (pin "44") (pinfunction "P4.1/TB0.1_44") (pintype "passive"))
    )
    (net (code "73") (name "/JG2-TB0.2") (class "Default")
      (node (ref "U2") (pin "45") (pinfunction "P4.2/TB0.2_45") (pintype "passive"))
    )
    (net (code "74") (name "/JG3-TB0.3") (class "Default")
      (node (ref "U2") (pin "46") (pinfunction "P4.3/TB0.3_46") (pintype "passive"))
      (node (ref "U4") (pin "5") (pinfunction "INC_5") (pintype "passive"))
    )
    (net (code "75") (name "/JG4-TB0.4") (class "Default")
      (node (ref "U2") (pin "47") (pinfunction "P4.4/TB0.4_47") (pintype "passive"))
      (node (ref "U4") (pin "6") (pinfunction "IND_6") (pintype "passive"))
    )
    (net (code "76") (name "/JG5-TB0.5") (class "Default")
      (node (ref "U2") (pin "48") (pinfunction "P4.5/TB0.5_48") (pintype "passive"))
    )
    (net (code "77") (name "/JG6-TB0.6") (class "Default")
      (node (ref "U2") (pin "49") (pinfunction "P4.6/TB0.6_49") (pintype "passive"))
    )
    (net (code "78") (name "/JG7") (class "Default")
      (node (ref "U2") (pin "50") (pinfunction "P4.7/TB0CLK/SMCLK_50") (pintype "passive"))
    )
    (net (code "79") (name "/LED0") (class "Default")
      (node (ref "U2") (pin "9") (pinfunction "P5.0/A8/VREF+/VeREF+_9") (pintype "passive"))
    )
    (net (code "80") (name "/LED1") (class "Default")
      (node (ref "U2") (pin "10") (pinfunction "P5.1/A9/VREF-/VeREF-_10") (pintype "passive"))
    )
    (net (code "81") (name "/M1") (class "Default")
      (node (ref "U3") (pin "8") (pinfunction "M1_8") (pintype "passive"))
      (node (ref "U5") (pin "14") (pinfunction "OUTA_14") (pintype "passive"))
    )
    (net (code "82") (name "/M2") (class "Default")
      (node (ref "U3") (pin "9") (pinfunction "M2_9") (pintype "passive"))
      (node (ref "U5") (pin "13") (pinfunction "OUTB_13") (pintype "passive"))
    )
    (net (code "83") (name "/M3") (class "Default")
      (node (ref "U3") (pin "10") (pinfunction "M3_10") (pintype "passive"))
      (node (ref "U5") (pin "12") (pinfunction "OUTC_12") (pintype "passive"))
    )
    (net (code "84") (name "/OUTC") (class "Default")
      (node (ref "L2") (pin "2") (pinfunction "2_2") (pintype "passive"))
      (node (ref "OUTPUT") (pin "2") (pinfunction "2_2") (pintype "passive"))
    )
    (net (code "85") (name "/OUTD") (class "Default")
      (node (ref "L1") (pin "2") (pinfunction "2_2") (pintype "passive"))
      (node (ref "OUTPUT") (pin "1") (pinfunction "1_1") (pintype "passive"))
    )
    (net (code "86") (name "/PWM-C") (class "Default")
      (node (ref "U3") (pin "7") (pinfunction "PWM-C_7") (pintype "passive"))
      (node (ref "U4") (pin "12") (pinfunction "OUTC_12") (pintype "passive"))
    )
    (net (code "87") (name "/PWM-D") (class "Default")
      (node (ref "U3") (pin "5") (pinfunction "PWM-D_5") (pintype "passive"))
      (node (ref "U4") (pin "11") (pinfunction "OUTD_11") (pintype "passive"))
    )
    (net (code "88") (name "/TCK") (class "Default")
      (node (ref "JTAG1") (pin "7") (pinfunction "7_7") (pintype "passive"))
      (node (ref "U2") (pin "95") (pinfunction "PJ.3/TCK_95") (pintype "passive"))
    )
    (net (code "89") (name "/TDI") (class "Default")
      (node (ref "JTAG1") (pin "3") (pinfunction "3_3") (pintype "passive"))
      (node (ref "U2") (pin "93") (pinfunction "PJ.1/TDI/TCLK_93") (pintype "passive"))
    )
    (net (code "90") (name "/TDO") (class "Default")
      (node (ref "JTAG1") (pin "1") (pinfunction "1_1") (pintype "passive"))
      (node (ref "U2") (pin "92") (pinfunction "PJ.0/TDO_92") (pintype "passive"))
    )
    (net (code "91") (name "/TEST") (class "Default")
      (node (ref "JTAG1") (pin "8") (pinfunction "8_8") (pintype "passive"))
      (node (ref "U2") (pin "91") (pinfunction "TEST/SBWTCK_91") (pintype "passive"))
    )
    (net (code "92") (name "/TMS") (class "Default")
      (node (ref "JTAG1") (pin "5") (pinfunction "5_5") (pintype "passive"))
      (node (ref "U2") (pin "94") (pinfunction "PJ.2/TMS_94") (pintype "passive"))
    )
    (net (code "93") (name "/UDP-SCK") (class "Default")
      (node (ref "U2") (pin "79") (pinfunction "P10.3/UCB3CLK/UCA3STE_79") (pintype "passive"))
    )
    (net (code "94") (name "/UDP-SIMO") (class "Default")
      (node (ref "U2") (pin "77") (pinfunction "P10.1/UCB3SIMO/UCB3SDA_77") (pintype "passive"))
    )
    (net (code "95") (name "/UDP-SOMI") (class "Default")
      (node (ref "U2") (pin "78") (pinfunction "P10.2/UCB3SOMI/UCB3SCL_78") (pintype "passive"))
    )
    (net (code "96") (name "/UDP-{slash}CS") (class "Default")
      (node (ref "U2") (pin "76") (pinfunction "P10.0/UCB3STE/UCA3CLK_76") (pintype "passive"))
    )
    (net (code "97") (name "/UDP-{slash}INT") (class "Default")
      (node (ref "U2") (pin "17") (pinfunction "P1.0/TA0CLK/ACLK_17") (pintype "passive"))
    )
    (net (code "98") (name "/UDP-{slash}RST") (class "Default")
      (node (ref "U2") (pin "75") (pinfunction "P9.7_75") (pintype "passive"))
    )
    (net (code "99") (name "/UDP-{slash}WOL") (class "Default")
      (node (ref "U2") (pin "25") (pinfunction "P2.0/TA1CLK/MCLK_25") (pintype "passive"))
    )
    (net (code "100") (name "/USB-RXD") (class "Default")
      (node (ref "U2") (pin "54") (pinfunction "P5.7/UCA1RXD/UCA1SOMI_54") (pintype "passive"))
    )
    (net (code "101") (name "/USB-TXD") (class "Default")
      (node (ref "U2") (pin "53") (pinfunction "P5.6/UCA1TXD/UCA1SIMO_53") (pintype "passive"))
    )
    (net (code "102") (name "/V1") (class "Default")
      (node (ref "R13") (pin "1") (pinfunction "1_1") (pintype "passive"))
      (node (ref "R15") (pin "2") (pinfunction "2_2") (pintype "passive"))
      (node (ref "R19") (pin "1") (pinfunction "1_1") (pintype "passive"))
      (node (ref "R21") (pin "2") (pinfunction "2_2") (pintype "passive"))
    )
    (net (code "103") (name "/V2") (class "Default")
      (node (ref "R16") (pin "2") (pinfunction "2_2") (pintype "passive"))
      (node (ref "R22") (pin "2") (pinfunction "2_2") (pintype "passive"))
      (node (ref "R25") (pin "1") (pinfunction "1_1") (pintype "passive"))
      (node (ref "R27") (pin "2") (pinfunction "2_2") (pintype "passive"))
    )
    (net (code "104") (name "/V3") (class "Default")
      (node (ref "R14") (pin "1") (pinfunction "1_1") (pintype "passive"))
      (node (ref "R17") (pin "2") (pinfunction "2_2") (pintype "passive"))
      (node (ref "R20") (pin "2") (pinfunction "2_2") (pintype "passive"))
      (node (ref "R23") (pin "2") (pinfunction "2_2") (pintype "passive"))
    )
    (net (code "105") (name "/V4") (class "Default")
      (node (ref "R18") (pin "2") (pinfunction "2_2") (pintype "passive"))
      (node (ref "R24") (pin "2") (pinfunction "2_2") (pintype "passive"))
      (node (ref "R26") (pin "2") (pinfunction "2_2") (pintype "passive"))
      (node (ref "R28") (pin "2") (pinfunction "2_2") (pintype "passive"))
    )
    (net (code "106") (name "/VCORE") (class "Default")
      (node (ref "C23") (pin "1") (pinfunction "1_1") (pintype "passive"))
      (node (ref "U2") (pin "62") (pinfunction "VCORE_62") (pintype "passive"))
    )
    (net (code "107") (name "/VREG") (class "Default")
      (node (ref "C17") (pin "2") (pinfunction "2_2") (pintype "passive"))
      (node (ref "U3") (pin "11") (pinfunction "VREG_11") (pintype "passive"))
    )
    (net (code "108") (name "/XIN") (class "Default")
      (node (ref "U2") (pin "13") (pinfunction "P7.0/XIN_13") (pintype "passive"))
      (node (ref "XTAL2") (pin "2") (pinfunction "OSC2_2") (pintype "passive"))
    )
    (net (code "109") (name "/XOUT") (class "Default")
      (node (ref "U2") (pin "14") (pinfunction "P7.1/XOUT_14") (pintype "passive"))
      (node (ref "XTAL2") (pin "1") (pinfunction "OSC1_1") (pintype "passive"))
    )
    (net (code "110") (name "/XT2IN") (class "Default")
      (node (ref "C1") (pin "2") (pinfunction "2_2") (pintype "passive"))
      (node (ref "U2") (pin "89") (pinfunction "P5.2/XT2IN_89") (pintype "passive"))
      (node (ref "XTAL1") (pin "2") (pinfunction "OSC2_2") (pintype "passive"))
    )
    (net (code "111") (name "/XT2OUT") (class "Default")
      (node (ref "C2") (pin "2") (pinfunction "2_2") (pintype "passive"))
      (node (ref "U2") (pin "90") (pinfunction "P5.3/XT2OUT_90") (pintype "passive"))
      (node (ref "XTAL1") (pin "1") (pinfunction "OSC1_1") (pintype "passive"))
    )
    (net (code "112") (name "/{slash}FAULT") (class "Default")
      (node (ref "R1") (pin "2") (pinfunction "2_2") (pintype "passive"))
      (node (ref "U3") (pin "18") (pinfunction "~{FAULT}_18") (pintype "passive"))
      (node (ref "U6") (pin "2") (pinfunction "INA_2") (pintype "passive"))
    )
    (net (code "113") (name "/{slash}OTW") (class "Default")
      (node (ref "R2") (pin "2") (pinfunction "2_2") (pintype "passive"))
      (node (ref "U3") (pin "21") (pinfunction "~{OTW}_21") (pintype "passive"))
      (node (ref "U6") (pin "3") (pinfunction "INB_3") (pintype "passive"))
    )
    (net (code "114") (name "/{slash}RESET") (class "Default")
      (node (ref "U3") (pin "16") (pinfunction "~{RESET-AB}_16") (pintype "passive"))
      (node (ref "U3") (pin "6") (pinfunction "~{RESET-CD}_6") (pintype "passive"))
      (node (ref "U5") (pin "11") (pinfunction "OUTD_11") (pintype "passive"))
    )
    (net (code "115") (name "/{slash}RST") (class "Default")
      (node (ref "AN1") (pin "2") (pinfunction "2_2") (pintype "passive"))
      (node (ref "C8") (pin "2") (pinfunction "2_2") (pintype "passive"))
      (node (ref "JTAG1") (pin "11") (pinfunction "11_11") (pintype "passive"))
      (node (ref "R7") (pin "1") (pinfunction "1_1") (pintype "passive"))
      (node (ref "U2") (pin "96") (pinfunction "~{RST}/NMI/SBWTDIO_96") (pintype "passive"))
    )
    (net (code "116") (name "GND") (class "Default")
      (node (ref "+12V") (pin "2") (pinfunction "2_2") (pintype "passive"))
      (node (ref "AN1") (pin "1") (pinfunction "1_1") (pintype "passive"))
      (node (ref "Button") (pin "11") (pinfunction "11_11") (pintype "passive"))
      (node (ref "Button") (pin "5") (pinfunction "5_5") (pintype "passive"))
      (node (ref "C1") (pin "1") (pinfunction "1_1") (pintype "passive"))
      (node (ref "C19") (pin "2") (pinfunction "2_2") (pintype "passive"))
      (node (ref "C2") (pin "1") (pinfunction "1_1") (pintype "passive"))
      (node (ref "C20") (pin "2") (pinfunction "2_2") (pintype "passive"))
      (node (ref "C21") (pin "2") (pinfunction "2_2") (pintype "passive"))
      (node (ref "C22") (pin "2") (pinfunction "2_2") (pintype "passive"))
      (node (ref "C23") (pin "2") (pinfunction "2_2") (pintype "passive"))
      (node (ref "C28") (pin "2") (pinfunction "2_2") (pintype "passive"))
      (node (ref "C29") (pin "1") (pinfunction "1_1") (pintype "passive"))
      (node (ref "C31") (pin "2") (pinfunction "2_2") (pintype "passive"))
      (node (ref "C32") (pin "2") (pinfunction "2_2") (pintype "passive"))
      (node (ref "C35") (pin "1") (pinfunction "1_1") (pintype "passive"))
      (node (ref "C36") (pin "1") (pinfunction "1_1") (pintype "passive"))
      (node (ref "C37") (pin "1") (pinfunction "1_1") (pintype "passive"))
      (node (ref "C38") (pin "1") (pinfunction "1_1") (pintype "passive"))
      (node (ref "C39") (pin "1") (pinfunction "1_1") (pintype "passive"))
      (node (ref "C8") (pin "1") (pinfunction "1_1") (pintype "passive"))
      (node (ref "D2") (pin "1") (pinfunction "A_1") (pintype "passive"))
      (node (ref "JTAG1") (pin "9") (pinfunction "9_9") (pintype "passive"))
      (node (ref "LED5") (pin "2") (pinfunction "K_2") (pintype "passive"))
      (node (ref "R27") (pin "1") (pinfunction "1_1") (pintype "passive"))
      (node (ref "R28") (pin "1") (pinfunction "1_1") (pintype "passive"))
      (node (ref "R30") (pin "1") (pinfunction "1_1") (pintype "passive"))
      (node (ref "R32") (pin "1") (pinfunction "1_1") (pintype "passive"))
      (node (ref "R35") (pin "1") (pinfunction "1_1") (pintype "passive"))
      (node (ref "RW2") (pin "1") (pinfunction "1_1") (pintype "passive"))
      (node (ref "RW3") (pin "1") (pinfunction "1_1") (pintype "passive"))
      (node (ref "RW4") (pin "1") (pinfunction "1_1") (pintype "passive"))
      (node (ref "RW5") (pin "1") (pinfunction "1_1") (pintype "passive"))
      (node (ref "U2") (pin "12") (pinfunction "AVSS_12") (pintype "passive"))
      (node (ref "U2") (pin "15") (pinfunction "DVSS1_15") (pintype "passive"))
      (node (ref "U2") (pin "37") (pinfunction "DVSS3_37") (pintype "passive"))
      (node (ref "U2") (pin "63") (pinfunction "DVSS2_63") (pintype "passive"))
      (node (ref "U2") (pin "88") (pinfunction "DVSS4_88") (pintype "passive"))
      (node (ref "U4") (pin "2") (pinfunction "GND1_2") (pintype "passive"))
      (node (ref "U4") (pin "8") (pinfunction "GND1_8") (pintype "passive"))
      (node (ref "U5") (pin "2") (pinfunction "GND1_2") (pintype "passive"))
      (node (ref "U5") (pin "8") (pinfunction "GND1_8") (pintype "passive"))
      (node (ref "U6") (pin "5") (pinfunction "GND2_5") (pintype "passive"))
      (node (ref "U7") (pin "6") (pinfunction "GND_6") (pintype "passive"))
      (node (ref "U7") (pin "9") (pinfunction "PowerPAD_9") (pintype "passive"))
      (node (ref "U8") (pin "3") (pinfunction "GND_3") (pintype "passive"))
      (node (ref "U9") (pin "4") (pinfunction "V-_4") (pintype "power_in"))
    )
    (net (code "117") (name "GND1") (class "Default")
      (node (ref "+12V1") (pin "2") (pinfunction "2_2") (pintype "passive"))
      (node (ref "C10") (pin "1") (pinfunction "1_1") (pintype "passive"))
      (node (ref "C11") (pin "1") (pinfunction "1_1") (pintype "passive"))
      (node (ref "C13") (pin "2") (pinfunction "2_2") (pintype "passive"))
      (node (ref "C14") (pin "1") (pinfunction "1_1") (pintype "passive"))
      (node (ref "C16") (pin "1") (pinfunction "1_1") (pintype "passive"))
      (node (ref "C18") (pin "1") (pinfunction "1_1") (pintype "passive"))
      (node (ref "C24") (pin "1") (pinfunction "1_1") (pintype "passive"))
      (node (ref "C26") (pin "1") (pinfunction "1_1") (pintype "passive"))
      (node (ref "C27") (pin "1") (pinfunction "1_1") (pintype "passive"))
      (node (ref "C3") (pin "2") (pinfunction "2_2") (pintype "passive"))
      (node (ref "C4") (pin "1") (pinfunction "1_1") (pintype "passive"))
      (node (ref "C5") (pin "2") (pinfunction "2_2") (pintype "passive"))
      (node (ref "C6") (pin "2") (pinfunction "2_2") (pintype "passive"))
      (node (ref "C7") (pin "1") (pinfunction "1_1") (pintype "passive"))
      (node (ref "C9") (pin "1") (pinfunction "1_1") (pintype "passive"))
      (node (ref "LED1") (pin "2") (pinfunction "K_2") (pintype "passive"))
      (node (ref "LED2") (pin "2") (pinfunction "K_2") (pintype "passive"))
      (node (ref "LED3") (pin "2") (pinfunction "K_2") (pintype "passive"))
      (node (ref "LED4") (pin "2") (pinfunction "K_2") (pintype "passive"))
      (node (ref "R8") (pin "2") (pinfunction "2_2") (pintype "passive"))
      (node (ref "U1") (pin "1") (pinfunction "GND_1") (pintype "power_in"))
      (node (ref "U3") (pin "13") (pinfunction "GND_13") (pintype "passive"))
      (node (ref "U3") (pin "29") (pinfunction "GND-A_29") (pintype "passive"))
      (node (ref "U3") (pin "30") (pinfunction "GND-B_30") (pintype "passive"))
      (node (ref "U3") (pin "37") (pinfunction "GND-C_37") (pintype "passive"))
      (node (ref "U3") (pin "38") (pinfunction "GND-D_38") (pintype "passive"))
      (node (ref "U3") (pin "45") (pinfunction "POWERPAD_45") (pintype "passive"))
      (node (ref "U4") (pin "10") (pinfunction "CTRL_10") (pintype "passive"))
      (node (ref "U4") (pin "15") (pinfunction "GND2_15") (pintype "passive"))
      (node (ref "U4") (pin "9") (pinfunction "GND2_9") (pintype "passive"))
      (node (ref "U5") (pin "10") (pinfunction "CTRL_10") (pintype "passive"))
      (node (ref "U5") (pin "15") (pinfunction "GND2_15") (pintype "passive"))
      (node (ref "U5") (pin "9") (pinfunction "GND2_9") (pintype "passive"))
      (node (ref "U6") (pin "4") (pinfunction "GND1_4") (pintype "passive"))
    )
    (net (code "118") (name "Net-(C40-Pad2)") (class "Default")
      (node (ref "C40") (pin "2") (pinfunction "2_2") (pintype "passive"))
      (node (ref "R34") (pin "1") (pinfunction "1_1") (pintype "passive"))
      (node (ref "R35") (pin "2") (pinfunction "2_2") (pintype "passive"))
    )
    (net (code "119") (name "Net-(D3-A)") (class "Default")
      (node (ref "C30") (pin "2") (pinfunction "2_2") (pintype "passive"))
      (node (ref "D3") (pin "1") (pinfunction "A_1") (pintype "passive"))
      (node (ref "R12") (pin "1") (pinfunction "1_1") (pintype "passive"))
    )
    (net (code "120") (name "Net-(LED1-A)") (class "Default")
      (node (ref "LED1") (pin "1") (pinfunction "A_1") (pintype "passive"))
      (node (ref "R3") (pin "1") (pinfunction "1_1") (pintype "passive"))
    )
    (net (code "121") (name "Net-(LED2-A)") (class "Default")
      (node (ref "LED2") (pin "1") (pinfunction "A_1") (pintype "passive"))
      (node (ref "R4") (pin "2") (pinfunction "2_2") (pintype "passive"))
    )
    (net (code "122") (name "Net-(LED3-A)") (class "Default")
      (node (ref "LED3") (pin "1") (pinfunction "A_1") (pintype "passive"))
      (node (ref "R5") (pin "2") (pinfunction "2_2") (pintype "passive"))
    )
    (net (code "123") (name "Net-(LED4-A)") (class "Default")
      (node (ref "LED4") (pin "1") (pinfunction "A_1") (pintype "passive"))
      (node (ref "R6") (pin "2") (pinfunction "2_2") (pintype "passive"))
    )
    (net (code "124") (name "Net-(LED5-A)") (class "Default")
      (node (ref "LED5") (pin "1") (pinfunction "A_1") (pintype "passive"))
      (node (ref "R10") (pin "2") (pinfunction "2_2") (pintype "passive"))
    )
    (net (code "125") (name "Net-(Q1-B)") (class "Default")
      (node (ref "Q1") (pin "2") (pinfunction "B_2") (pintype "passive"))
      (node (ref "R1") (pin "1") (pinfunction "1_1") (pintype "passive"))
    )
    (net (code "126") (name "Net-(Q1-C)") (class "Default")
      (node (ref "Q1") (pin "1") (pinfunction "C_1") (pintype "passive"))
      (node (ref "R5") (pin "1") (pinfunction "1_1") (pintype "passive"))
    )
    (net (code "127") (name "Net-(Q2-B)") (class "Default")
      (node (ref "Q2") (pin "2") (pinfunction "B_2") (pintype "passive"))
      (node (ref "R2") (pin "1") (pinfunction "1_1") (pintype "passive"))
    )
    (net (code "128") (name "Net-(Q2-C)") (class "Default")
      (node (ref "Q2") (pin "1") (pinfunction "C_1") (pintype "passive"))
      (node (ref "R6") (pin "1") (pinfunction "1_1") (pintype "passive"))
    )
    (net (code "129") (name "Net-(R9-Pad1)") (class "Default")
      (node (ref "R9") (pin "1") (pinfunction "1_1") (pintype "passive"))
      (node (ref "RW1") (pin "1") (pinfunction "1_1") (pintype "passive"))
    )
    (net (code "130") (name "Net-(R21-Pad1)") (class "Default")
      (node (ref "R21") (pin "1") (pinfunction "1_1") (pintype "passive"))
      (node (ref "RW2") (pin "2") (pinfunction "2_2") (pintype "passive"))
      (node (ref "RW2") (pin "3") (pinfunction "3_3") (pintype "passive"))
    )
    (net (code "131") (name "Net-(R22-Pad1)") (class "Default")
      (node (ref "R22") (pin "1") (pinfunction "1_1") (pintype "passive"))
      (node (ref "RW3") (pin "2") (pinfunction "2_2") (pintype "passive"))
      (node (ref "RW3") (pin "3") (pinfunction "3_3") (pintype "passive"))
    )
    (net (code "132") (name "Net-(R23-Pad1)") (class "Default")
      (node (ref "R23") (pin "1") (pinfunction "1_1") (pintype "passive"))
      (node (ref "RW4") (pin "2") (pinfunction "2_2") (pintype "passive"))
      (node (ref "RW4") (pin "3") (pinfunction "3_3") (pintype "passive"))
    )
    (net (code "133") (name "Net-(R24-Pad1)") (class "Default")
      (node (ref "R24") (pin "1") (pinfunction "1_1") (pintype "passive"))
      (node (ref "RW5") (pin "2") (pinfunction "2_2") (pintype "passive"))
      (node (ref "RW5") (pin "3") (pinfunction "3_3") (pintype "passive"))
    )
    (net (code "134") (name "Net-(R29-Pad1)") (class "Default")
      (node (ref "R29") (pin "1") (pinfunction "1_1") (pintype "passive"))
      (node (ref "RW6") (pin "3") (pinfunction "3_3") (pintype "passive"))
    )
    (net (code "135") (name "Net-(R30-Pad2)") (class "Default")
      (node (ref "R30") (pin "2") (pinfunction "2_2") (pintype "passive"))
      (node (ref "RW6") (pin "1") (pinfunction "1_1") (pintype "passive"))
    )
    (net (code "136") (name "Net-(R31-Pad1)") (class "Default")
      (node (ref "R31") (pin "1") (pinfunction "1_1") (pintype "passive"))
      (node (ref "RW7") (pin "3") (pinfunction "3_3") (pintype "passive"))
    )
    (net (code "137") (name "Net-(R32-Pad2)") (class "Default")
      (node (ref "R32") (pin "2") (pinfunction "2_2") (pintype "passive"))
      (node (ref "RW7") (pin "1") (pinfunction "1_1") (pintype "passive"))
    )
    (net (code "138") (name "Net-(R33-Pad2)") (class "Default")
      (node (ref "R33") (pin "2") (pinfunction "2_2") (pintype "passive"))
      (node (ref "RW7") (pin "2") (pinfunction "2_2") (pintype "passive"))
    )
    (net (code "139") (name "Net-(R36-Pad1)") (class "Default")
      (node (ref "R36") (pin "1") (pinfunction "1_1") (pintype "passive"))
      (node (ref "RW8") (pin "3") (pinfunction "3_3") (pintype "passive"))
    )
    (net (code "140") (name "Net-(U3-AGND)") (class "Default")
      (node (ref "C17") (pin "1") (pinfunction "1_1") (pintype "passive"))
      (node (ref "R8") (pin "1") (pinfunction "1_1") (pintype "passive"))
      (node (ref "RW1") (pin "2") (pinfunction "2_2") (pintype "passive"))
      (node (ref "RW1") (pin "3") (pinfunction "3_3") (pintype "passive"))
      (node (ref "U3") (pin "12") (pinfunction "AGND_12") (pintype "passive"))
    )
    (net (code "141") (name "Net-(U3-OC-ADJ)") (class "Default")
      (node (ref "R9") (pin "2") (pinfunction "2_2") (pintype "passive"))
      (node (ref "U3") (pin "14") (pinfunction "OC-ADJ_14") (pintype "passive"))
    )
    (net (code "142") (name "Net-(U3-OUT-C)") (class "Default")
      (node (ref "C15") (pin "2") (pinfunction "2_2") (pintype "passive"))
      (node (ref "L2") (pin "1") (pinfunction "1_1") (pintype "passive"))
      (node (ref "U3") (pin "36") (pinfunction "OUT-C_36") (pintype "passive"))
    )
    (net (code "143") (name "Net-(U3-OUT-D)") (class "Default")
      (node (ref "C12") (pin "1") (pinfunction "1_1") (pintype "passive"))
      (node (ref "L1") (pin "1") (pinfunction "1_1") (pintype "passive"))
      (node (ref "U3") (pin "39") (pinfunction "OUT-D_39") (pintype "passive"))
    )
    (net (code "144") (name "Net-(U7-BOOT)") (class "Default")
      (node (ref "C25") (pin "1") (pinfunction "1_1") (pintype "passive"))
      (node (ref "U7") (pin "1") (pinfunction "BOOT_1") (pintype "passive"))
    )
    (net (code "145") (name "Net-(U7-VSENSE)") (class "Default")
      (node (ref "R11") (pin "1") (pinfunction "1_1") (pintype "passive"))
      (node (ref "R12") (pin "2") (pinfunction "2_2") (pintype "passive"))
      (node (ref "U7") (pin "4") (pinfunction "VSENSE_4") (pintype "passive"))
    )
    (net (code "146") (name "Net-(U9A-INA+)") (class "Default")
      (node (ref "R33") (pin "1") (pinfunction "1_1") (pintype "passive"))
      (node (ref "U9") (pin "3") (pinfunction "INA+_3") (pintype "input"))
    )
    (net (code "147") (name "Net-(U9A-INA-)") (class "Default")
      (node (ref "R34") (pin "2") (pinfunction "2_2") (pintype "passive"))
      (node (ref "R36") (pin "2") (pinfunction "2_2") (pintype "passive"))
      (node (ref "U9") (pin "2") (pinfunction "INA-_2") (pintype "input"))
    )
    (net (code "148") (name "VIN") (class "Default")
      (node (ref "C28") (pin "1") (pinfunction "1_1") (pintype "passive"))
      (node (ref "C29") (pin "2") (pinfunction "2_2") (pintype "passive"))
      (node (ref "D1") (pin "2") (pinfunction "K_2") (pintype "passive"))
      (node (ref "D2") (pin "2") (pinfunction "K_2") (pintype "passive"))
      (node (ref "R10") (pin "1") (pinfunction "1_1") (pintype "passive"))
      (node (ref "U7") (pin "7") (pinfunction "VIN_7") (pintype "passive"))
    )
    (net (code "149") (name "VPH") (class "Default")
      (node (ref "C25") (pin "2") (pinfunction "2_2") (pintype "passive"))
      (node (ref "D3") (pin "2") (pinfunction "K_2") (pintype "passive"))
      (node (ref "L3") (pin "1") (pinfunction "1_1") (pintype "passive"))
      (node (ref "U7") (pin "8") (pinfunction "PH_8") (pintype "passive"))
    )
    (net (code "150") (name "unconnected-(JTAG1-Pad2)") (class "Default")
      (node (ref "JTAG1") (pin "2") (pinfunction "2_2") (pintype "passive"))
    )
    (net (code "151") (name "unconnected-(JTAG1-Pad6)") (class "Default")
      (node (ref "JTAG1") (pin "6") (pinfunction "6_6") (pintype "passive"))
    )
    (net (code "152") (name "unconnected-(JTAG1-Pad10)") (class "Default")
      (node (ref "JTAG1") (pin "10") (pinfunction "10_10") (pintype "passive"))
    )
    (net (code "153") (name "unconnected-(JTAG1-Pad12)") (class "Default")
      (node (ref "JTAG1") (pin "12") (pinfunction "12_12") (pintype "passive"))
    )
    (net (code "154") (name "unconnected-(JTAG1-Pad13)") (class "Default")
      (node (ref "JTAG1") (pin "13") (pinfunction "13_13") (pintype "passive"))
    )
    (net (code "155") (name "unconnected-(JTAG1-Pad14)") (class "Default")
      (node (ref "JTAG1") (pin "14") (pinfunction "14_14") (pintype "passive"))
    )
    (net (code "156") (name "unconnected-(U3-BST-A-Pad24)") (class "Default")
      (node (ref "U3") (pin "24") (pinfunction "BST-A_24") (pintype "passive"))
    )
    (net (code "157") (name "unconnected-(U3-BST-B-Pad33)") (class "Default")
      (node (ref "U3") (pin "33") (pinfunction "BST-B_33") (pintype "passive"))
    )
    (net (code "158") (name "unconnected-(U3-NC-Pad3)") (class "Default")
      (node (ref "U3") (pin "3") (pinfunction "NC_3") (pintype "passive"))
    )
    (net (code "159") (name "unconnected-(U3-NC-Pad4)") (class "Default")
      (node (ref "U3") (pin "4") (pinfunction "NC_4") (pintype "passive"))
    )
    (net (code "160") (name "unconnected-(U3-NC-Pad19)") (class "Default")
      (node (ref "U3") (pin "19") (pinfunction "NC_19") (pintype "passive"))
    )
    (net (code "161") (name "unconnected-(U3-NC-Pad20)") (class "Default")
      (node (ref "U3") (pin "20") (pinfunction "NC_20") (pintype "passive"))
    )
    (net (code "162") (name "unconnected-(U3-NC-Pad25)") (class "Default")
      (node (ref "U3") (pin "25") (pinfunction "NC_25") (pintype "passive"))
    )
    (net (code "163") (name "unconnected-(U3-NC-Pad42)") (class "Default")
      (node (ref "U3") (pin "42") (pinfunction "NC_42") (pintype "passive"))
    )
    (net (code "164") (name "unconnected-(U3-OUT-A-Pad28)") (class "Default")
      (node (ref "U3") (pin "28") (pinfunction "OUT-A_28") (pintype "passive"))
    )
    (net (code "165") (name "unconnected-(U3-OUT-B-Pad31)") (class "Default")
      (node (ref "U3") (pin "31") (pinfunction "OUT-B_31") (pintype "passive"))
    )
    (net (code "166") (name "unconnected-(U3-PWM-A-Pad17)") (class "Default")
      (node (ref "U3") (pin "17") (pinfunction "PWM-A_17") (pintype "passive"))
    )
    (net (code "167") (name "unconnected-(U3-PWM-B-Pad15)") (class "Default")
      (node (ref "U3") (pin "15") (pinfunction "PWM-B_15") (pintype "passive"))
    )
    (net (code "168") (name "unconnected-(U4-DISABLE-Pad7)") (class "Default")
      (node (ref "U4") (pin "7") (pinfunction "DISABLE_7") (pintype "passive"))
    )
    (net (code "169") (name "unconnected-(U4-INA-Pad3)") (class "Default")
      (node (ref "U4") (pin "3") (pinfunction "INA_3") (pintype "passive"))
    )
    (net (code "170") (name "unconnected-(U4-INB-Pad4)") (class "Default")
      (node (ref "U4") (pin "4") (pinfunction "INB_4") (pintype "passive"))
    )
    (net (code "171") (name "unconnected-(U4-OUTA-Pad14)") (class "Default")
      (node (ref "U4") (pin "14") (pinfunction "OUTA_14") (pintype "passive"))
    )
    (net (code "172") (name "unconnected-(U4-OUTB-Pad13)") (class "Default")
      (node (ref "U4") (pin "13") (pinfunction "OUTB_13") (pintype "passive"))
    )
    (net (code "173") (name "unconnected-(U5-DISABLE-Pad7)") (class "Default")
      (node (ref "U5") (pin "7") (pinfunction "DISABLE_7") (pintype "passive"))
    )
    (net (code "174") (name "unconnected-(U7-ENA-Pad5)") (class "Default")
      (node (ref "U7") (pin "5") (pinfunction "ENA_5") (pintype "passive"))
    )
    (net (code "175") (name "unconnected-(U7-NC-Pad2)") (class "Default")
      (node (ref "U7") (pin "2") (pinfunction "NC_2") (pintype "passive"))
    )
    (net (code "176") (name "unconnected-(U7-NC-Pad3)") (class "Default")
      (node (ref "U7") (pin "3") (pinfunction "NC_3") (pintype "passive"))
    )
  )
)
